# Analog_isolation.net
KiCad netlist of a schematic drawn in Altium Designer
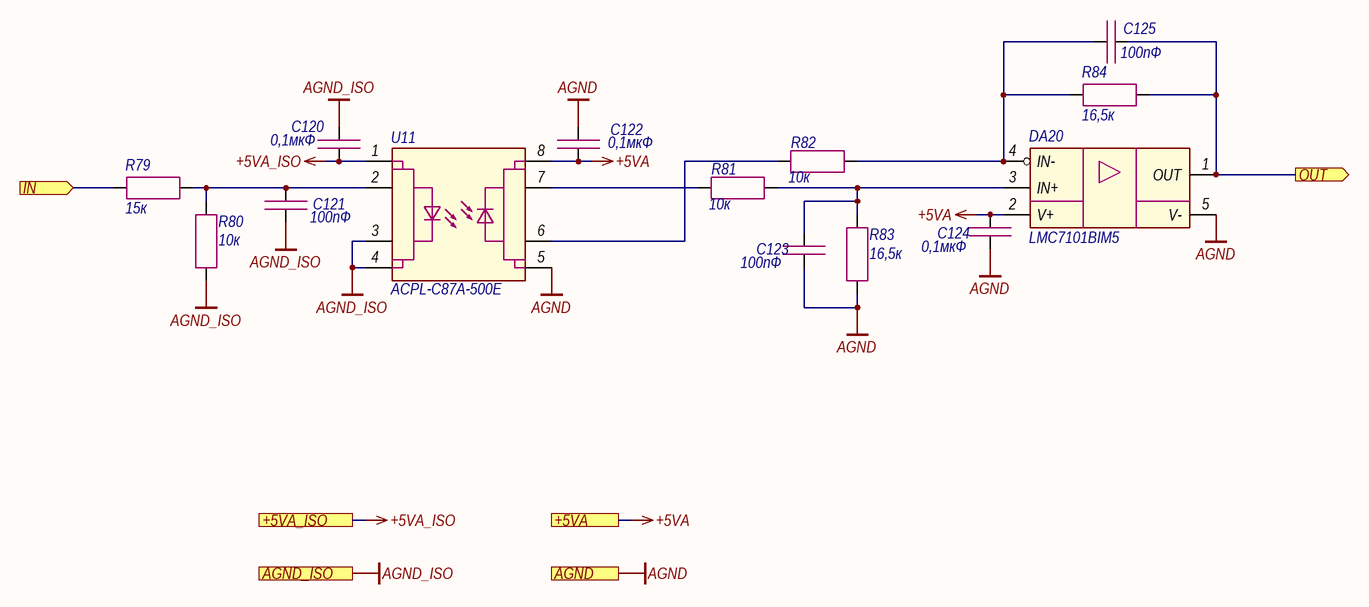
[diagram p0: Analog_isolation.SchDoc]

(export (version "E")
  (design (tool "Eeschema 10.0.6"))
  (components
    (comp (ref "C120")
      (value "0,1мкФ")
      (footprint "Pcb_library:CAP_0603")
      (fields (field (name "MANUFACTURER") "Murata"))
      (libsource (lib "Schem_library") (part "Capacitor"))
    )
    (comp (ref "C121")
      (value "100пФ")
      (footprint "Pcb_library:CAP_0603")
      (fields (field (name "MANUFACTURER") "Murata"))
      (libsource (lib "Schem_library") (part "Capacitor"))
    )
    (comp (ref "C122")
      (value "0,1мкФ")
      (footprint "Pcb_library:CAP_0603")
      (fields (field (name "MANUFACTURER") "Murata"))
      (libsource (lib "Schem_library") (part "Capacitor"))
    )
    (comp (ref "C123")
      (value "100пФ")
      (footprint "Pcb_library:CAP_0603")
      (fields (field (name "MANUFACTURER") "Murata"))
      (libsource (lib "Schem_library") (part "Capacitor"))
    )
    (comp (ref "C124")
      (value "0,1мкФ")
      (footprint "Pcb_library:CAP_0603")
      (fields (field (name "MANUFACTURER") "Murata"))
      (libsource (lib "Schem_library") (part "Capacitor"))
    )
    (comp (ref "C125")
      (value "100пФ")
      (footprint "Pcb_library:CAP_0603")
      (fields (field (name "MANUFACTURER") "Murata"))
      (libsource (lib "Schem_library") (part "Capacitor"))
    )
    (comp (ref "DA20")
      (value "LMC7101BIM5")
      (footprint "Pcb_library:SOT-23-5")
      (fields (field (name "MANUFACTURER") "Texas Instruments"))
      (libsource (lib "Schem_library") (part "LMC7101"))
    )
    (comp (ref "R79")
      (value "15к")
      (footprint "Pcb_library:RES_0603")
      (fields (field (name "MANUFACTURER") "Yageo"))
      (libsource (lib "Schem_library") (part "Resistor"))
    )
    (comp (ref "R80")
      (value "10к")
      (footprint "Pcb_library:RES_0603")
      (fields (field (name "MANUFACTURER") "Yageo"))
      (libsource (lib "Schem_library") (part "Resistor"))
    )
    (comp (ref "R81")
      (value "10к")
      (footprint "Pcb_library:RES_0603")
      (fields (field (name "MANUFACTURER") "Yageo"))
      (libsource (lib "Schem_library") (part "Resistor"))
    )
    (comp (ref "R82")
      (value "10к")
      (footprint "Pcb_library:RES_0603")
      (fields (field (name "MANUFACTURER") "Yageo"))
      (libsource (lib "Schem_library") (part "Resistor"))
    )
    (comp (ref "R83")
      (value "16,5к")
      (footprint "Pcb_library:RES_0603")
      (fields (field (name "MANUFACTURER") "Yageo"))
      (libsource (lib "Schem_library") (part "Resistor"))
    )
    (comp (ref "R84")
      (value "16,5к")
      (footprint "Pcb_library:RES_0603")
      (fields (field (name "MANUFACTURER") "Yageo"))
      (libsource (lib "Schem_library") (part "Resistor"))
    )
    (comp (ref "U11")
      (value "ACPL-C87A-500E")
      (footprint "Pcb_library:SSO-8")
      (fields (field (name "MANUFACTURER") "Broadcom"))
      (libsource (lib "Schem_library") (part "ACPL-C87"))
    )
  )
  (nets
    (net (code "1") (name "+5VA") (class "Default")
      (node (ref "C122") (pin "1") (pinfunction "1_1") (pintype "passive"))
      (node (ref "C124") (pin "1") (pinfunction "1_1") (pintype "passive"))
      (node (ref "DA20") (pin "2") (pinfunction "V+_2") (pintype "passive"))
      (node (ref "U11") (pin "8") (pinfunction "VDD2_8") (pintype "passive"))
    )
    (net (code "2") (name "+5VA_ISO") (class "Default")
      (node (ref "C120") (pin "1") (pinfunction "1_1") (pintype "passive"))
      (node (ref "U11") (pin "1") (pinfunction "VDD1_1") (pintype "passive"))
    )
    (net (code "3") (name "/IN") (class "Default")
      (node (ref "R79") (pin "2") (pinfunction "2_2") (pintype "passive"))
    )
    (net (code "4") (name "/OUT") (class "Default")
      (node (ref "C125") (pin "2") (pinfunction "2_2") (pintype "passive"))
      (node (ref "DA20") (pin "1") (pinfunction "OUT_1") (pintype "passive"))
      (node (ref "R84") (pin "1") (pinfunction "1_1") (pintype "passive"))
    )
    (net (code "5") (name "AGND") (class "Default")
      (node (ref "C122") (pin "2") (pinfunction "2_2") (pintype "passive"))
      (node (ref "C123") (pin "2") (pinfunction "2_2") (pintype "passive"))
      (node (ref "C124") (pin "2") (pinfunction "2_2") (pintype "passive"))
      (node (ref "DA20") (pin "5") (pinfunction "V-_5") (pintype "passive"))
      (node (ref "R83") (pin "2") (pinfunction "2_2") (pintype "passive"))
      (node (ref "U11") (pin "5") (pinfunction "GND2_5") (pintype "passive"))
    )
    (net (code "6") (name "AGND_ISO") (class "Default")
      (node (ref "C120") (pin "2") (pinfunction "2_2") (pintype "passive"))
      (node (ref "C121") (pin "1") (pinfunction "1_1") (pintype "passive"))
      (node (ref "R80") (pin "2") (pinfunction "2_2") (pintype "passive"))
      (node (ref "U11") (pin "3") (pinfunction "SHDN_3") (pintype "passive"))
      (node (ref "U11") (pin "4") (pinfunction "GND1_4") (pintype "passive"))
    )
    (net (code "7") (name "Net-(DA20-IN+)") (class "Default")
      (node (ref "C123") (pin "1") (pinfunction "1_1") (pintype "passive"))
      (node (ref "DA20") (pin "3") (pinfunction "IN+_3") (pintype "passive"))
      (node (ref "R81") (pin "2") (pinfunction "2_2") (pintype "passive"))
      (node (ref "R83") (pin "1") (pinfunction "1_1") (pintype "passive"))
    )
    (net (code "8") (name "Net-(DA20-IN-)") (class "Default")
      (node (ref "C125") (pin "1") (pinfunction "1_1") (pintype "passive"))
      (node (ref "DA20") (pin "4") (pinfunction "IN-_4") (pintype "passive"))
      (node (ref "R82") (pin "2") (pinfunction "2_2") (pintype "passive"))
      (node (ref "R84") (pin "2") (pinfunction "2_2") (pintype "passive"))
    )
    (net (code "9") (name "Net-(U11-VIN)") (class "Default")
      (node (ref "C121") (pin "2") (pinfunction "2_2") (pintype "passive"))
      (node (ref "R79") (pin "1") (pinfunction "1_1") (pintype "passive"))
      (node (ref "R80") (pin "1") (pinfunction "1_1") (pintype "passive"))
      (node (ref "U11") (pin "2") (pinfunction "VIN_2") (pintype "passive"))
    )
    (net (code "10") (name "Net-(U11-VOUT+)") (class "Default")
      (node (ref "R81") (pin "1") (pinfunction "1_1") (pintype "passive"))
      (node (ref "U11") (pin "7") (pinfunction "VOUT+_7") (pintype "passive"))
    )
    (net (code "11") (name "Net-(U11-VOUT-)") (class "Default")
      (node (ref "R82") (pin "1") (pinfunction "1_1") (pintype "passive"))
      (node (ref "U11") (pin "6") (pinfunction "VOUT-_6") (pintype "passive"))
    )
  )
)
